# EN-C200_RA0_OLED.net
KiCad netlist of a schematic drawn in Altium Designer
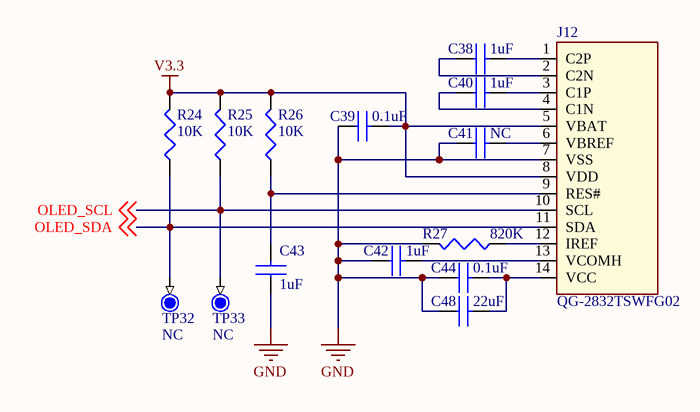
[diagram p0: EN-C200_RA0_OLED.SchDoc]

(export (version "E")
  (design (tool "Eeschema 10.0.6"))
  (components
    (comp (ref "C38") (value "1uF") (footprint "SC0603") (libsource (lib "EN-C200_RA0") (part "CAP NP")))
    (comp (ref "C39") (value "0.1uF") (footprint "SC0603") (libsource (lib "EN-C200_RA0") (part "CAP NP")))
    (comp (ref "C40") (value "1uF") (footprint "SC0603") (libsource (lib "EN-C200_RA0") (part "CAP NP")))
    (comp (ref "C41") (value "NC") (footprint "SC0603") (libsource (lib "EN-C200_RA0") (part "CAP NP")))
    (comp (ref "C42") (value "1uF") (footprint "SC0603") (libsource (lib "EN-C200_RA0") (part "CAP NP")))
    (comp (ref "C43") (value "1uF") (footprint "SC0603") (libsource (lib "EN-C200_RA0") (part "CAP NP")))
    (comp (ref "C44") (value "0.1uF") (footprint "SC0603") (libsource (lib "EN-C200_RA0") (part "CAP NP")))
    (comp (ref "C48") (value "22uF") (footprint "SC0805") (libsource (lib "EN-C200_RA0") (part "CAP NP")))
    (comp (ref "J12")
      (value "QG-2832TSWFG02")
      (footprint "FPC14-25")
      (libsource (lib "EN-C200_RA0") (part "OLED_0.91"))
    )
    (comp (ref "R24") (value "10K") (footprint "SR0603") (libsource (lib "EN-C200_RA0") (part "RESISTOR")))
    (comp (ref "R25") (value "10K") (footprint "SR0603") (libsource (lib "EN-C200_RA0") (part "RESISTOR")))
    (comp (ref "R26") (value "10K") (footprint "SR0603") (libsource (lib "EN-C200_RA0") (part "RESISTOR")))
    (comp (ref "R27") (value "820K") (footprint "SR0603") (libsource (lib "EN-C200_RA0") (part "RESISTOR")))
    (comp (ref "TP32") (value "NC") (footprint "TP32-SMD") (libsource (lib "EN-C200_RA0") (part "TP")))
    (comp (ref "TP33") (value "NC") (footprint "TP32-SMD") (libsource (lib "EN-C200_RA0") (part "TP")))
  )
  (nets
    (net (code "1") (name "GND") (class "Default")
      (node (ref "C39") (pin "1") (pinfunction "1_1") (pintype "passive"))
      (node (ref "C41") (pin "1") (pinfunction "1_1") (pintype "passive"))
      (node (ref "C42") (pin "1") (pinfunction "1_1") (pintype "passive"))
      (node (ref "C43") (pin "1") (pinfunction "1_1") (pintype "passive"))
      (node (ref "C44") (pin "1") (pinfunction "1_1") (pintype "passive"))
      (node (ref "C48") (pin "1") (pinfunction "1_1") (pintype "passive"))
      (node (ref "J12") (pin "7") (pinfunction "VSS_7") (pintype "power_in"))
      (node (ref "R27") (pin "2") (pinfunction "2_2") (pintype "passive"))
    )
    (net (code "2") (name "Net-(J12-C1N)") (class "Default")
      (node (ref "C40") (pin "1") (pinfunction "1_1") (pintype "passive"))
      (node (ref "J12") (pin "4") (pinfunction "C1N_4") (pintype "passive"))
    )
    (net (code "3") (name "Net-(J12-C1P)") (class "Default")
      (node (ref "C40") (pin "2") (pinfunction "2_2") (pintype "passive"))
      (node (ref "J12") (pin "3") (pinfunction "C1P_3") (pintype "passive"))
    )
    (net (code "4") (name "Net-(J12-C2N)") (class "Default")
      (node (ref "C38") (pin "1") (pinfunction "1_1") (pintype "passive"))
      (node (ref "J12") (pin "2") (pinfunction "C2N_2") (pintype "passive"))
    )
    (net (code "5") (name "Net-(J12-C2P)") (class "Default")
      (node (ref "C38") (pin "2") (pinfunction "2_2") (pintype "passive"))
      (node (ref "J12") (pin "1") (pinfunction "C2P_1") (pintype "passive"))
    )
    (net (code "6") (name "Net-(J12-IREF)") (class "Default")
      (node (ref "J12") (pin "12") (pinfunction "IREF_12") (pintype "passive"))
      (node (ref "R27") (pin "1") (pinfunction "1_1") (pintype "passive"))
    )
    (net (code "7") (name "Net-(J12-RES#)") (class "Default")
      (node (ref "C43") (pin "2") (pinfunction "2_2") (pintype "passive"))
      (node (ref "J12") (pin "9") (pinfunction "RES#_9") (pintype "passive"))
      (node (ref "R26") (pin "1") (pinfunction "1_1") (pintype "passive"))
    )
    (net (code "8") (name "Net-(J12-VBREF)") (class "Default")
      (node (ref "C41") (pin "2") (pinfunction "2_2") (pintype "passive"))
      (node (ref "J12") (pin "6") (pinfunction "VBREF_6") (pintype "passive"))
    )
    (net (code "9") (name "Net-(J12-VCC)") (class "Default")
      (node (ref "C44") (pin "2") (pinfunction "2_2") (pintype "passive"))
      (node (ref "C48") (pin "2") (pinfunction "2_2") (pintype "passive"))
      (node (ref "J12") (pin "14") (pinfunction "VCC_14") (pintype "power_in"))
    )
    (net (code "10") (name "Net-(J12-VCOMH)") (class "Default")
      (node (ref "C42") (pin "2") (pinfunction "2_2") (pintype "passive"))
      (node (ref "J12") (pin "13") (pinfunction "VCOMH_13") (pintype "passive"))
    )
    (net (code "11") (name "OLED_SCL") (class "Default")
      (node (ref "J12") (pin "10") (pinfunction "SCL_10") (pintype "passive"))
      (node (ref "R25") (pin "1") (pinfunction "1_1") (pintype "passive"))
      (node (ref "TP33") (pin "1") (pinfunction "1_1") (pintype "input"))
    )
    (net (code "12") (name "OLED_SDA") (class "Default")
      (node (ref "J12") (pin "11") (pinfunction "SDA_11") (pintype "passive"))
      (node (ref "R24") (pin "1") (pinfunction "1_1") (pintype "passive"))
      (node (ref "TP32") (pin "1") (pinfunction "1_1") (pintype "input"))
    )
    (net (code "13") (name "V3.3") (class "Default")
      (node (ref "C39") (pin "2") (pinfunction "2_2") (pintype "passive"))
      (node (ref "J12") (pin "5") (pinfunction "VBAT_5") (pintype "passive"))
      (node (ref "J12") (pin "8") (pinfunction "VDD_8") (pintype "passive"))
      (node (ref "R24") (pin "2") (pinfunction "2_2") (pintype "passive"))
      (node (ref "R25") (pin "2") (pinfunction "2_2") (pintype "passive"))
      (node (ref "R26") (pin "2") (pinfunction "2_2") (pintype "passive"))
    )
  )
)
